# lather_front_panel.net
KiCad netlist of a schematic drawn in Altium Designer
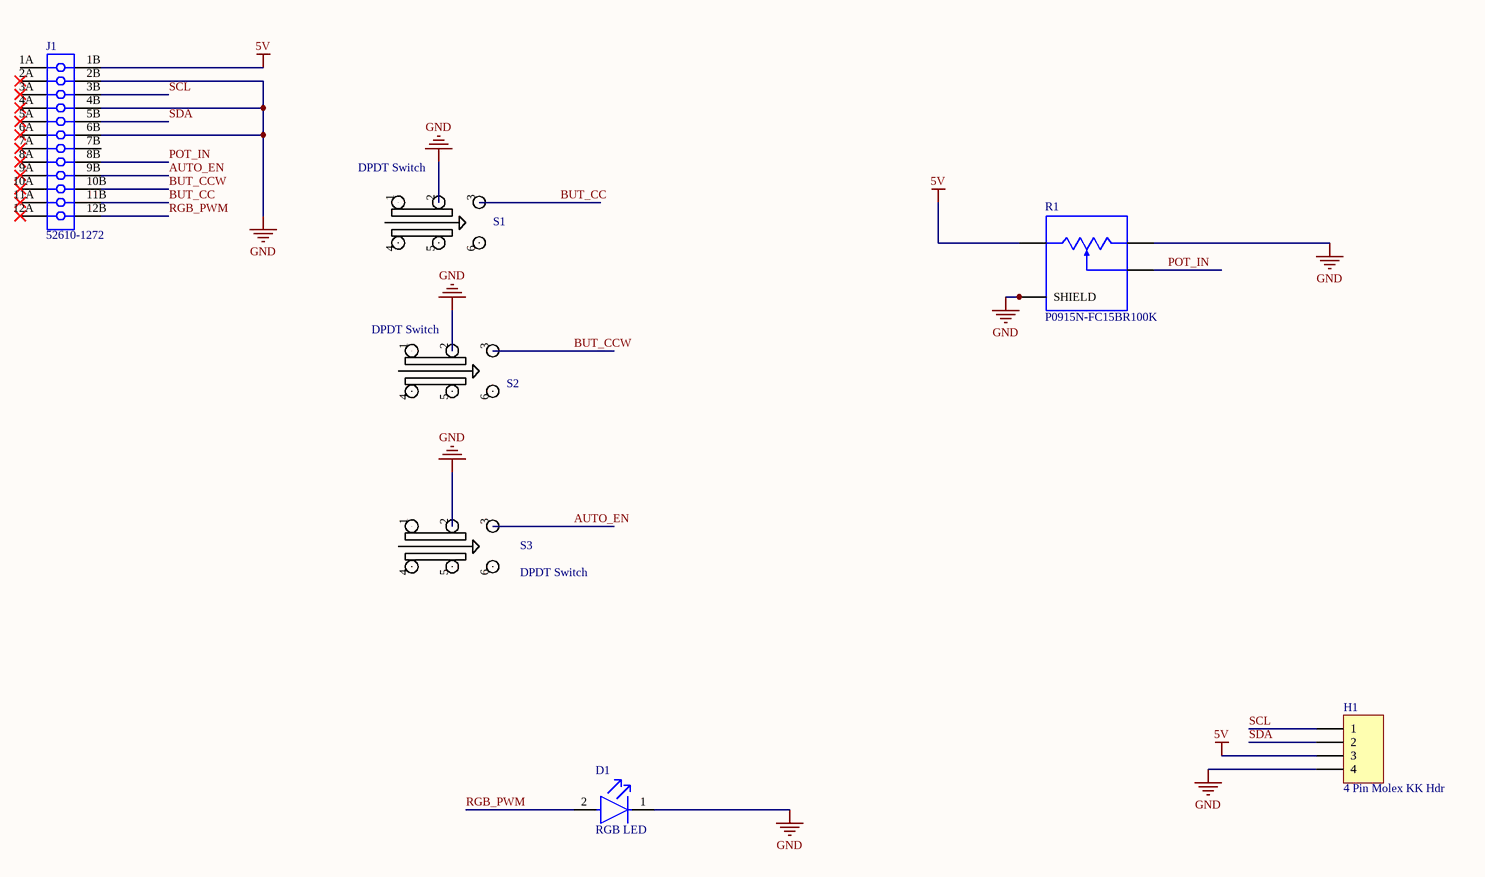
[diagram p0: lather_front_panel.SchDoc]

(export (version "E")
  (design (tool "Eeschema 10.0.6"))
  (components
    (comp (ref "D1")
      (value "RGB LED")
      (footprint "INDRD500W70D900H1220")
      (libsource (lib "lathe_library") (part "RGB LED"))
    )
    (comp (ref "H1")
      (value "4 Pin Molex KK Hdr")
      (footprint "MOLEX_KK_4_HDR")
      (description "CONN HEADER 4POS 2.54mm VERT_Thru Hole")
      (fields (field (name "MANUFACTURER") "Molex"))
      (libsource (lib "ECE AD19Components_22V1") (part "JA_MOLEX_KK_4POS"))
    )
    (comp (ref "J1")
      (value "52610-1272")
      (footprint "MOLX-52610-1272")
      (fields (field (name "MANUFACTURER") "Molex"))
      (libsource (lib "Altium Content Vault") (part "MOLX-52610-1272"))
    )
    (comp (ref "R1")
      (value "P0915N-FC15BR100K")
      (footprint "TRIM_P0915N-FC15BR100K")
      (fields (field (name "MF") "TT Electronics/BI"))
      (libsource (lib "lathe_library") (part "P0915N-FC15BR100K"))
    )
    (comp (ref "S1")
      (value "DPDT Switch")
      (footprint "TL2230EEF100")
      (libsource (lib "lathe_library") (part "TL2230EEF100"))
    )
    (comp (ref "S2")
      (value "DPDT Switch")
      (footprint "TL2230EEF100")
      (libsource (lib "lathe_library") (part "TL2230EEF100"))
    )
    (comp (ref "S3")
      (value "DPDT Switch")
      (footprint "TL2230EEF100")
      (libsource (lib "lathe_library") (part "TL2230EEF100"))
    )
  )
  (nets
    (net (code "1") (name "/AUTO_EN") (class "Default")
      (node (ref "J1") (pin "9B") (pinfunction "9B_9B") (pintype "passive"))
      (node (ref "S3") (pin "3") (pinfunction "3_3") (pintype "passive"))
    )
    (net (code "2") (name "/BUT_CC") (class "Default")
      (node (ref "J1") (pin "11B") (pinfunction "11B_11B") (pintype "passive"))
      (node (ref "S1") (pin "3") (pinfunction "3_3") (pintype "passive"))
    )
    (net (code "3") (name "/BUT_CCW") (class "Default")
      (node (ref "J1") (pin "10B") (pinfunction "10B_10B") (pintype "passive"))
      (node (ref "S2") (pin "3") (pinfunction "3_3") (pintype "passive"))
    )
    (net (code "4") (name "/POT_IN") (class "Default")
      (node (ref "J1") (pin "8B") (pinfunction "8B_8B") (pintype "passive"))
      (node (ref "R1") (pin "2") (pinfunction "2_2") (pintype "passive"))
    )
    (net (code "5") (name "/RGB_PWM") (class "Default")
      (node (ref "D1") (pin "2") (pinfunction "A_2") (pintype "passive"))
      (node (ref "J1") (pin "12B") (pinfunction "12B_12B") (pintype "passive"))
    )
    (net (code "6") (name "/SCL") (class "Default")
      (node (ref "H1") (pin "1") (pinfunction "1_1") (pintype "passive"))
      (node (ref "J1") (pin "3B") (pinfunction "3B_3B") (pintype "passive"))
    )
    (net (code "7") (name "/SDA") (class "Default")
      (node (ref "H1") (pin "2") (pinfunction "2_2") (pintype "passive"))
      (node (ref "J1") (pin "5B") (pinfunction "5B_5B") (pintype "passive"))
    )
    (net (code "8") (name "5V") (class "Default")
      (node (ref "H1") (pin "3") (pinfunction "3_3") (pintype "passive"))
      (node (ref "J1") (pin "1B") (pinfunction "1B_1B") (pintype "passive"))
      (node (ref "R1") (pin "1") (pinfunction "1_1") (pintype "passive"))
    )
    (net (code "9") (name "GND") (class "Default")
      (node (ref "D1") (pin "1") (pinfunction "C_1") (pintype "passive"))
      (node (ref "H1") (pin "4") (pinfunction "4_4") (pintype "passive"))
      (node (ref "J1") (pin "2B") (pinfunction "2B_2B") (pintype "passive"))
      (node (ref "J1") (pin "4B") (pinfunction "4B_4B") (pintype "passive"))
      (node (ref "J1") (pin "6B") (pinfunction "6B_6B") (pintype "passive"))
      (node (ref "R1") (pin "3") (pinfunction "3_3") (pintype "passive"))
      (node (ref "R1") (pin "S1") (pinfunction "SHIELD_S1") (pintype "passive"))
      (node (ref "R1") (pin "S2") (pinfunction "SHIELD_S2") (pintype "passive"))
      (node (ref "S1") (pin "2") (pinfunction "2_2") (pintype "passive"))
      (node (ref "S2") (pin "2") (pinfunction "2_2") (pintype "passive"))
      (node (ref "S3") (pin "2") (pinfunction "2_2") (pintype "passive"))
    )
    (net (code "10") (name "unconnected-(J1-Pad1A)") (class "Default")
      (node (ref "J1") (pin "1A") (pinfunction "1A_1A") (pintype "passive"))
    )
    (net (code "11") (name "unconnected-(J1-Pad2A)") (class "Default")
      (node (ref "J1") (pin "2A") (pinfunction "2A_2A") (pintype "passive+no_connect"))
    )
    (net (code "12") (name "unconnected-(J1-Pad3A)") (class "Default")
      (node (ref "J1") (pin "3A") (pinfunction "3A_3A") (pintype "passive+no_connect"))
    )
    (net (code "13") (name "unconnected-(J1-Pad4A)") (class "Default")
      (node (ref "J1") (pin "4A") (pinfunction "4A_4A") (pintype "passive+no_connect"))
    )
    (net (code "14") (name "unconnected-(J1-Pad5A)") (class "Default")
      (node (ref "J1") (pin "5A") (pinfunction "5A_5A") (pintype "passive+no_connect"))
    )
    (net (code "15") (name "unconnected-(J1-Pad6A)") (class "Default")
      (node (ref "J1") (pin "6A") (pinfunction "6A_6A") (pintype "passive+no_connect"))
    )
    (net (code "16") (name "unconnected-(J1-Pad7A)") (class "Default")
      (node (ref "J1") (pin "7A") (pinfunction "7A_7A") (pintype "passive+no_connect"))
    )
    (net (code "17") (name "unconnected-(J1-Pad7B)") (class "Default")
      (node (ref "J1") (pin "7B") (pinfunction "7B_7B") (pintype "passive"))
    )
    (net (code "18") (name "unconnected-(J1-Pad8A)") (class "Default")
      (node (ref "J1") (pin "8A") (pinfunction "8A_8A") (pintype "passive+no_connect"))
    )
    (net (code "19") (name "unconnected-(J1-Pad9A)") (class "Default")
      (node (ref "J1") (pin "9A") (pinfunction "9A_9A") (pintype "passive+no_connect"))
    )
    (net (code "20") (name "unconnected-(J1-Pad10A)") (class "Default")
      (node (ref "J1") (pin "10A") (pinfunction "10A_10A") (pintype "passive+no_connect"))
    )
    (net (code "21") (name "unconnected-(J1-Pad11A)") (class "Default")
      (node (ref "J1") (pin "11A") (pinfunction "11A_11A") (pintype "passive+no_connect"))
    )
    (net (code "22") (name "unconnected-(J1-Pad12A)") (class "Default")
      (node (ref "J1") (pin "12A") (pinfunction "12A_12A") (pintype "passive+no_connect"))
    )
    (net (code "23") (name "unconnected-(S1-Pad1)") (class "Default")
      (node (ref "S1") (pin "1") (pinfunction "1_1") (pintype "passive"))
    )
    (net (code "24") (name "unconnected-(S1-Pad4)") (class "Default")
      (node (ref "S1") (pin "4") (pinfunction "4_4") (pintype "passive"))
    )
    (net (code "25") (name "unconnected-(S1-Pad5)") (class "Default")
      (node (ref "S1") (pin "5") (pinfunction "5_5") (pintype "passive"))
    )
    (net (code "26") (name "unconnected-(S1-Pad6)") (class "Default")
      (node (ref "S1") (pin "6") (pinfunction "6_6") (pintype "passive"))
    )
    (net (code "27") (name "unconnected-(S2-Pad1)") (class "Default")
      (node (ref "S2") (pin "1") (pinfunction "1_1") (pintype "passive"))
    )
    (net (code "28") (name "unconnected-(S2-Pad4)") (class "Default")
      (node (ref "S2") (pin "4") (pinfunction "4_4") (pintype "passive"))
    )
    (net (code "29") (name "unconnected-(S2-Pad5)") (class "Default")
      (node (ref "S2") (pin "5") (pinfunction "5_5") (pintype "passive"))
    )
    (net (code "30") (name "unconnected-(S2-Pad6)") (class "Default")
      (node (ref "S2") (pin "6") (pinfunction "6_6") (pintype "passive"))
    )
    (net (code "31") (name "unconnected-(S3-Pad1)") (class "Default")
      (node (ref "S3") (pin "1") (pinfunction "1_1") (pintype "passive"))
    )
    (net (code "32") (name "unconnected-(S3-Pad4)") (class "Default")
      (node (ref "S3") (pin "4") (pinfunction "4_4") (pintype "passive"))
    )
    (net (code "33") (name "unconnected-(S3-Pad5)") (class "Default")
      (node (ref "S3") (pin "5") (pinfunction "5_5") (pintype "passive"))
    )
    (net (code "34") (name "unconnected-(S3-Pad6)") (class "Default")
      (node (ref "S3") (pin "6") (pinfunction "6_6") (pintype "passive"))
    )
  )
)
